# Mako_DSP_Audio_Codec_R1_1.net
KiCad netlist of a schematic drawn in Altium Designer
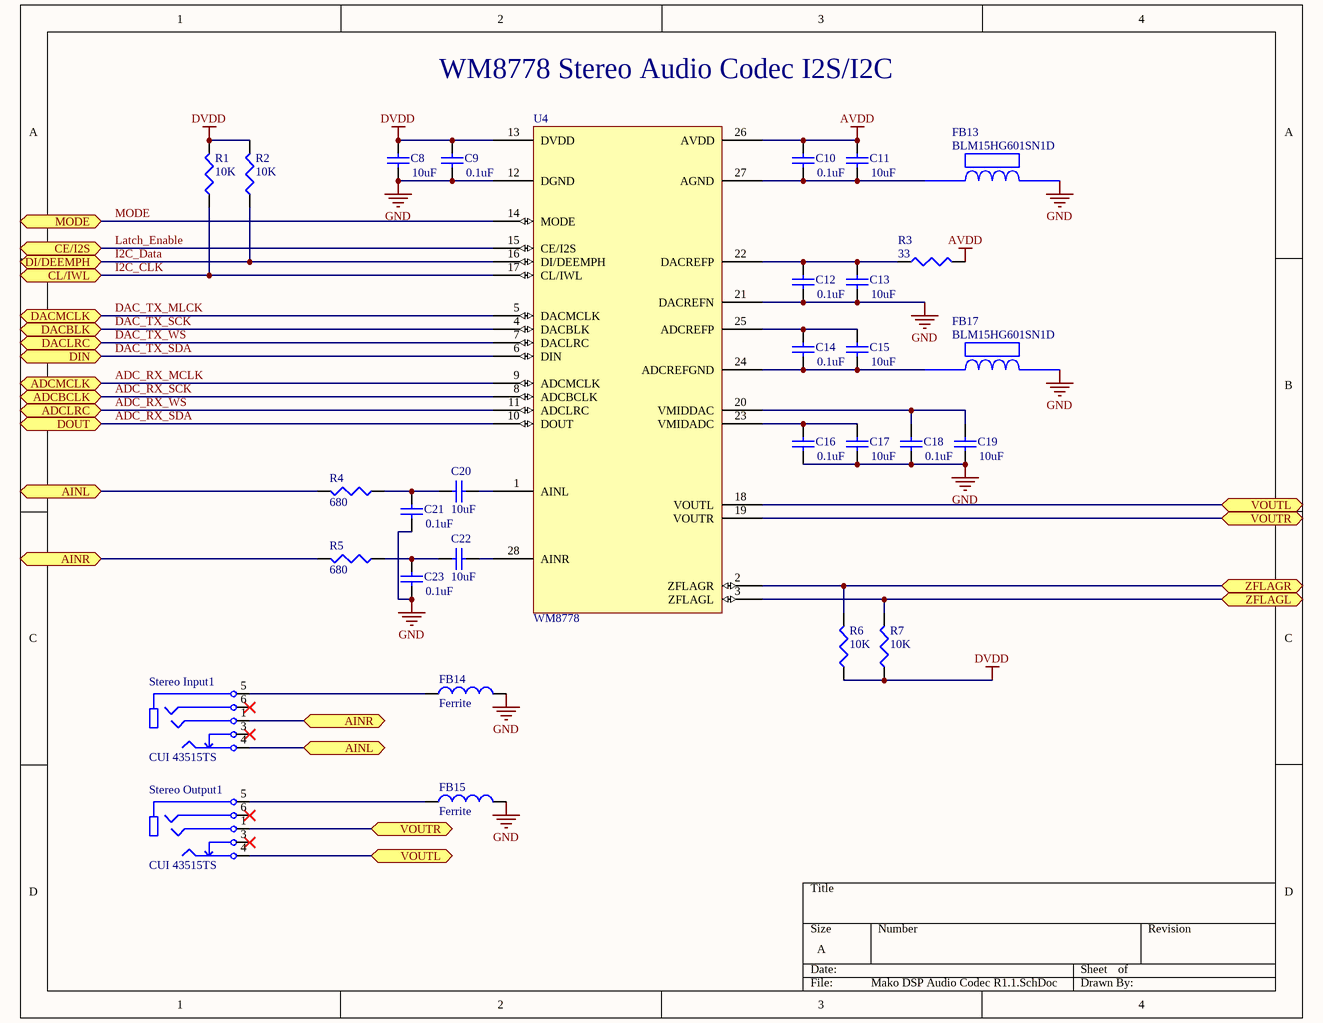
[diagram p0: Mako DSP Audio Codec R1.1.SchDoc]

(export (version "E")
  (design (tool "Eeschema 10.0.6"))
  (components
    (comp (ref "C8")
      (value "10uF")
      (footprint "1608[0603]")
      (description "Capacitor (Semiconductor SIM Model)")
      (fields (field (name "Comment") "Cap Semi") (field (name "PUBLISHER") "Altium Limited"))
      (libsource (lib "Miscellaneous Devices") (part "Cap Semi"))
    )
    (comp (ref "C9")
      (value "0.1uF")
      (footprint "1608[0603]")
      (description "Capacitor (Semiconductor SIM Model)")
      (fields (field (name "Comment") "Cap Semi") (field (name "PUBLISHER") "Altium Limited"))
      (libsource (lib "Miscellaneous Devices") (part "Cap Semi"))
    )
    (comp (ref "C10")
      (value "0.1uF")
      (footprint "1608[0603]")
      (description "Capacitor (Semiconductor SIM Model)")
      (fields (field (name "Comment") "Cap Semi") (field (name "PUBLISHER") "Altium Limited"))
      (libsource (lib "Miscellaneous Devices") (part "Cap Semi"))
    )
    (comp (ref "C11")
      (value "10uF")
      (footprint "1608[0603]")
      (description "Capacitor (Semiconductor SIM Model)")
      (fields (field (name "Comment") "Cap Semi") (field (name "PUBLISHER") "Altium Limited"))
      (libsource (lib "Miscellaneous Devices") (part "Cap Semi"))
    )
    (comp (ref "C12")
      (value "0.1uF")
      (footprint "1608[0603]")
      (description "Capacitor (Semiconductor SIM Model)")
      (fields (field (name "Comment") "Cap Semi") (field (name "PUBLISHER") "Altium Limited"))
      (libsource (lib "Miscellaneous Devices") (part "Cap Semi"))
    )
    (comp (ref "C13")
      (value "10uF")
      (footprint "1608[0603]")
      (description "Capacitor (Semiconductor SIM Model)")
      (fields (field (name "Comment") "Cap Semi") (field (name "PUBLISHER") "Altium Limited"))
      (libsource (lib "Miscellaneous Devices") (part "Cap Semi"))
    )
    (comp (ref "C14")
      (value "0.1uF")
      (footprint "1608[0603]")
      (description "Capacitor (Semiconductor SIM Model)")
      (fields (field (name "Comment") "Cap Semi") (field (name "PUBLISHER") "Altium Limited"))
      (libsource (lib "Miscellaneous Devices") (part "Cap Semi"))
    )
    (comp (ref "C15")
      (value "10uF")
      (footprint "1608[0603]")
      (description "Capacitor (Semiconductor SIM Model)")
      (fields (field (name "Comment") "Cap Semi") (field (name "PUBLISHER") "Altium Limited"))
      (libsource (lib "Miscellaneous Devices") (part "Cap Semi"))
    )
    (comp (ref "C16")
      (value "0.1uF")
      (footprint "1608[0603]")
      (description "Capacitor (Semiconductor SIM Model)")
      (fields (field (name "Comment") "Cap Semi") (field (name "PUBLISHER") "Altium Limited"))
      (libsource (lib "Miscellaneous Devices") (part "Cap Semi"))
    )
    (comp (ref "C17")
      (value "10uF")
      (footprint "1608[0603]")
      (description "Capacitor (Semiconductor SIM Model)")
      (fields (field (name "Comment") "Cap Semi") (field (name "PUBLISHER") "Altium Limited"))
      (libsource (lib "Miscellaneous Devices") (part "Cap Semi"))
    )
    (comp (ref "C18")
      (value "0.1uF")
      (footprint "1608[0603]")
      (description "Capacitor (Semiconductor SIM Model)")
      (fields (field (name "Comment") "Cap Semi") (field (name "PUBLISHER") "Altium Limited"))
      (libsource (lib "Miscellaneous Devices") (part "Cap Semi"))
    )
    (comp (ref "C19")
      (value "10uF")
      (footprint "1608[0603]")
      (description "Capacitor (Semiconductor SIM Model)")
      (fields (field (name "Comment") "Cap Semi") (field (name "PUBLISHER") "Altium Limited"))
      (libsource (lib "Miscellaneous Devices") (part "Cap Semi"))
    )
    (comp (ref "C20")
      (value "10uF")
      (footprint "Panasonic VS B")
      (description "Capacitor (Semiconductor SIM Model)")
      (fields (field (name "Comment") "Cap Semi") (field (name "PUBLISHER") "Altium Limited"))
      (libsource (lib "Miscellaneous Devices") (part "Cap Semi"))
    )
    (comp (ref "C21")
      (value "0.1uF")
      (footprint "SM 0805 - gap trimmed")
      (description "Capacitor (Semiconductor SIM Model)")
      (fields (field (name "Comment") "Cap Semi") (field (name "PUBLISHER") "Altium Limited"))
      (libsource (lib "Miscellaneous Devices") (part "Cap Semi"))
    )
    (comp (ref "C22")
      (value "10uF")
      (footprint "Panasonic VS B")
      (description "Capacitor (Semiconductor SIM Model)")
      (fields (field (name "Comment") "Cap Semi") (field (name "PUBLISHER") "Altium Limited"))
      (libsource (lib "Miscellaneous Devices") (part "Cap Semi"))
    )
    (comp (ref "C23")
      (value "0.1uF")
      (footprint "SM 0805 - gap trimmed")
      (description "Capacitor (Semiconductor SIM Model)")
      (fields (field (name "Comment") "Cap Semi") (field (name "PUBLISHER") "Altium Limited"))
      (libsource (lib "Miscellaneous Devices") (part "Cap Semi"))
    )
    (comp (ref "FB13")
      (value "BLM15HG601SN1D")
      (footprint "BLM18PG121SN1D")
      (libsource (lib "AHD Part Library") (part "BLM15HG601SN1D"))
    )
    (comp (ref "FB14")
      (value "Ferrite")
      (footprint "SM 0805 - gap trimmed")
      (description "Inductor")
      (fields (field (name "PUBLISHER") "Altium Limited"))
      (libsource (lib "Miscellaneous Devices") (part "Inductor"))
    )
    (comp (ref "FB15")
      (value "Ferrite")
      (footprint "SM 0805 - gap trimmed")
      (description "Inductor")
      (fields (field (name "PUBLISHER") "Altium Limited"))
      (libsource (lib "Miscellaneous Devices") (part "Inductor"))
    )
    (comp (ref "FB17")
      (value "BLM15HG601SN1D")
      (footprint "BLM18PG121SN1D")
      (libsource (lib "AHD Part Library") (part "BLM15HG601SN1D"))
    )
    (comp (ref "R1")
      (value "10K")
      (footprint "J1-0603")
      (description "Resistor")
      (fields (field (name "Comment") "Res3") (field (name "PUBLISHER") "Altium Limited"))
      (libsource (lib "Miscellaneous Devices") (part "Res3"))
    )
    (comp (ref "R2")
      (value "10K")
      (footprint "J1-0603")
      (description "Resistor")
      (fields (field (name "Comment") "Res3") (field (name "PUBLISHER") "Altium Limited"))
      (libsource (lib "Miscellaneous Devices") (part "Res3"))
    )
    (comp (ref "R3")
      (value "33")
      (footprint "J1-0603")
      (description "Resistor")
      (fields (field (name "Comment") "Res3") (field (name "PUBLISHER") "Altium Limited"))
      (libsource (lib "Miscellaneous Devices") (part "Res3"))
    )
    (comp (ref "R4")
      (value "680")
      (footprint "SM 0805 - gap trimmed")
      (description "Resistor")
      (fields (field (name "Comment") "Res3") (field (name "PUBLISHER") "Altium Limited"))
      (libsource (lib "Miscellaneous Devices") (part "Res3"))
    )
    (comp (ref "R5")
      (value "680")
      (footprint "SM 0805 - gap trimmed")
      (description "Resistor")
      (fields (field (name "Comment") "Res3") (field (name "PUBLISHER") "Altium Limited"))
      (libsource (lib "Miscellaneous Devices") (part "Res3"))
    )
    (comp (ref "R6")
      (value "10K")
      (footprint "J1-0603")
      (description "Resistor")
      (fields (field (name "Comment") "Res3") (field (name "PUBLISHER") "Altium Limited"))
      (libsource (lib "Miscellaneous Devices") (part "Res3"))
    )
    (comp (ref "R7")
      (value "10K")
      (footprint "J1-0603")
      (description "Resistor")
      (fields (field (name "Comment") "Res3") (field (name "PUBLISHER") "Altium Limited"))
      (libsource (lib "Miscellaneous Devices") (part "Res3"))
    )
    (comp (ref "Stereo Input1")
      (value "CUI 43515TS")
      (footprint "CUI SJ-43515TS")
      (libsource (lib "Adams Altium Library") (part "CUI 43515TS"))
    )
    (comp (ref "Stereo Output1")
      (value "CUI 43515TS")
      (footprint "CUI SJ-43515TS")
      (libsource (lib "Adams Altium Library") (part "CUI 43515TS"))
    )
    (comp (ref "U4")
      (value "WM8778")
      (footprint "WM8778")
      (libsource (lib "Mako DSP Schematic Library") (part "WM8778"))
    )
  )
  (nets
    (net (code "1") (name "/ADC_RX_MCLK") (class "Default")
      (node (ref "U4") (pin "9") (pinfunction "ADCMCLK_9") (pintype "bidirectional"))
    )
    (net (code "2") (name "/ADC_RX_SCK") (class "Default")
      (node (ref "U4") (pin "8") (pinfunction "ADCBCLK_8") (pintype "bidirectional"))
    )
    (net (code "3") (name "/ADC_RX_SDA") (class "Default")
      (node (ref "U4") (pin "10") (pinfunction "DOUT_10") (pintype "bidirectional"))
    )
    (net (code "4") (name "/ADC_RX_WS") (class "Default")
      (node (ref "U4") (pin "11") (pinfunction "ADCLRC_11") (pintype "bidirectional"))
    )
    (net (code "5") (name "/AINL") (class "Default")
      (node (ref "R4") (pin "2") (pinfunction "2_2") (pintype "passive"))
      (node (ref "Stereo Input1") (pin "4") (pinfunction "TIP_4") (pintype "passive"))
    )
    (net (code "6") (name "/AINR") (class "Default")
      (node (ref "R5") (pin "2") (pinfunction "2_2") (pintype "passive"))
      (node (ref "Stereo Input1") (pin "1") (pinfunction "R1_1") (pintype "passive"))
    )
    (net (code "7") (name "/DAC_TX_MLCK") (class "Default")
      (node (ref "U4") (pin "5") (pinfunction "DACMCLK_5") (pintype "bidirectional"))
    )
    (net (code "8") (name "/DAC_TX_SCK") (class "Default")
      (node (ref "U4") (pin "4") (pinfunction "DACBLK_4") (pintype "bidirectional"))
    )
    (net (code "9") (name "/DAC_TX_SDA") (class "Default")
      (node (ref "U4") (pin "6") (pinfunction "DIN_6") (pintype "bidirectional"))
    )
    (net (code "10") (name "/DAC_TX_WS") (class "Default")
      (node (ref "U4") (pin "7") (pinfunction "DACLRC_7") (pintype "bidirectional"))
    )
    (net (code "11") (name "/I2C_CLK") (class "Default")
      (node (ref "R1") (pin "1") (pinfunction "1_1") (pintype "passive"))
      (node (ref "U4") (pin "17") (pinfunction "CL/IWL_17") (pintype "bidirectional"))
    )
    (net (code "12") (name "/I2C_Data") (class "Default")
      (node (ref "R2") (pin "1") (pinfunction "1_1") (pintype "passive"))
      (node (ref "U4") (pin "16") (pinfunction "DI/DEEMPH_16") (pintype "bidirectional"))
    )
    (net (code "13") (name "/Latch_Enable") (class "Default")
      (node (ref "U4") (pin "15") (pinfunction "CE/I2S_15") (pintype "bidirectional"))
    )
    (net (code "14") (name "/MODE") (class "Default")
      (node (ref "U4") (pin "14") (pinfunction "MODE_14") (pintype "bidirectional"))
    )
    (net (code "15") (name "/VOUTL") (class "Default")
      (node (ref "Stereo Output1") (pin "4") (pinfunction "TIP_4") (pintype "passive"))
      (node (ref "U4") (pin "18") (pinfunction "VOUTL_18") (pintype "passive"))
    )
    (net (code "16") (name "/VOUTR") (class "Default")
      (node (ref "Stereo Output1") (pin "1") (pinfunction "R1_1") (pintype "passive"))
      (node (ref "U4") (pin "19") (pinfunction "VOUTR_19") (pintype "passive"))
    )
    (net (code "17") (name "/ZFLAGL") (class "Default")
      (node (ref "R7") (pin "2") (pinfunction "2_2") (pintype "passive"))
      (node (ref "U4") (pin "3") (pinfunction "ZFLAGL_3") (pintype "bidirectional"))
    )
    (net (code "18") (name "/ZFLAGR") (class "Default")
      (node (ref "R6") (pin "2") (pinfunction "2_2") (pintype "passive"))
      (node (ref "U4") (pin "2") (pinfunction "ZFLAGR_2") (pintype "bidirectional"))
    )
    (net (code "19") (name "AVDD") (class "Default")
      (node (ref "C10") (pin "2") (pinfunction "2_2") (pintype "passive"))
      (node (ref "C11") (pin "2") (pinfunction "2_2") (pintype "passive"))
      (node (ref "R3") (pin "2") (pinfunction "2_2") (pintype "passive"))
      (node (ref "U4") (pin "26") (pinfunction "AVDD_26") (pintype "passive"))
    )
    (net (code "20") (name "DVDD") (class "Default")
      (node (ref "C8") (pin "2") (pinfunction "2_2") (pintype "passive"))
      (node (ref "C9") (pin "2") (pinfunction "2_2") (pintype "passive"))
      (node (ref "R1") (pin "2") (pinfunction "2_2") (pintype "passive"))
      (node (ref "R2") (pin "2") (pinfunction "2_2") (pintype "passive"))
      (node (ref "R6") (pin "1") (pinfunction "1_1") (pintype "passive"))
      (node (ref "R7") (pin "1") (pinfunction "1_1") (pintype "passive"))
      (node (ref "U4") (pin "13") (pinfunction "DVDD_13") (pintype "passive"))
    )
    (net (code "21") (name "GND") (class "Default")
      (node (ref "C12") (pin "1") (pinfunction "1_1") (pintype "passive"))
      (node (ref "C13") (pin "1") (pinfunction "1_1") (pintype "passive"))
      (node (ref "C16") (pin "1") (pinfunction "1_1") (pintype "passive"))
      (node (ref "C17") (pin "1") (pinfunction "1_1") (pintype "passive"))
      (node (ref "C18") (pin "1") (pinfunction "1_1") (pintype "passive"))
      (node (ref "C19") (pin "1") (pinfunction "1_1") (pintype "passive"))
      (node (ref "C21") (pin "1") (pinfunction "1_1") (pintype "passive"))
      (node (ref "C23") (pin "1") (pinfunction "1_1") (pintype "passive"))
      (node (ref "C8") (pin "1") (pinfunction "1_1") (pintype "passive"))
      (node (ref "C9") (pin "1") (pinfunction "1_1") (pintype "passive"))
      (node (ref "FB13") (pin "2") (pinfunction "2_2") (pintype "passive"))
      (node (ref "FB14") (pin "2") (pinfunction "2_2") (pintype "passive"))
      (node (ref "FB15") (pin "2") (pinfunction "2_2") (pintype "passive"))
      (node (ref "FB17") (pin "2") (pinfunction "2_2") (pintype "passive"))
      (node (ref "U4") (pin "12") (pinfunction "DGND_12") (pintype "passive"))
      (node (ref "U4") (pin "21") (pinfunction "DACREFN_21") (pintype "passive"))
    )
    (net (code "22") (name "Net-(C20-Pad2)") (class "Default")
      (node (ref "C20") (pin "2") (pinfunction "2_2") (pintype "passive"))
      (node (ref "C21") (pin "2") (pinfunction "2_2") (pintype "passive"))
      (node (ref "R4") (pin "1") (pinfunction "1_1") (pintype "passive"))
    )
    (net (code "23") (name "Net-(C22-Pad2)") (class "Default")
      (node (ref "C22") (pin "2") (pinfunction "2_2") (pintype "passive"))
      (node (ref "C23") (pin "2") (pinfunction "2_2") (pintype "passive"))
      (node (ref "R5") (pin "1") (pinfunction "1_1") (pintype "passive"))
    )
    (net (code "24") (name "Net-(Stereo Input1-SLEEVE)") (class "Default")
      (node (ref "FB14") (pin "1") (pinfunction "1_1") (pintype "passive"))
      (node (ref "Stereo Input1") (pin "5") (pinfunction "SLEEVE_5") (pintype "passive"))
    )
    (net (code "25") (name "Net-(Stereo Output1-SLEEVE)") (class "Default")
      (node (ref "FB15") (pin "1") (pinfunction "1_1") (pintype "passive"))
      (node (ref "Stereo Output1") (pin "5") (pinfunction "SLEEVE_5") (pintype "passive"))
    )
    (net (code "26") (name "Net-(U4-ADCREFGND)") (class "Default")
      (node (ref "C14") (pin "1") (pinfunction "1_1") (pintype "passive"))
      (node (ref "C15") (pin "1") (pinfunction "1_1") (pintype "passive"))
      (node (ref "FB17") (pin "1") (pinfunction "1_1") (pintype "passive"))
      (node (ref "U4") (pin "24") (pinfunction "ADCREFGND_24") (pintype "passive"))
    )
    (net (code "27") (name "Net-(U4-ADCREFP)") (class "Default")
      (node (ref "C14") (pin "2") (pinfunction "2_2") (pintype "passive"))
      (node (ref "C15") (pin "2") (pinfunction "2_2") (pintype "passive"))
      (node (ref "U4") (pin "25") (pinfunction "ADCREFP_25") (pintype "passive"))
    )
    (net (code "28") (name "Net-(U4-AGND)") (class "Default")
      (node (ref "C10") (pin "1") (pinfunction "1_1") (pintype "passive"))
      (node (ref "C11") (pin "1") (pinfunction "1_1") (pintype "passive"))
      (node (ref "FB13") (pin "1") (pinfunction "1_1") (pintype "passive"))
      (node (ref "U4") (pin "27") (pinfunction "AGND_27") (pintype "passive"))
    )
    (net (code "29") (name "Net-(U4-AINL)") (class "Default")
      (node (ref "C20") (pin "1") (pinfunction "1_1") (pintype "passive"))
      (node (ref "U4") (pin "1") (pinfunction "AINL_1") (pintype "passive"))
    )
    (net (code "30") (name "Net-(U4-AINR)") (class "Default")
      (node (ref "C22") (pin "1") (pinfunction "1_1") (pintype "passive"))
      (node (ref "U4") (pin "28") (pinfunction "AINR_28") (pintype "passive"))
    )
    (net (code "31") (name "Net-(U4-DACREFP)") (class "Default")
      (node (ref "C12") (pin "2") (pinfunction "2_2") (pintype "passive"))
      (node (ref "C13") (pin "2") (pinfunction "2_2") (pintype "passive"))
      (node (ref "R3") (pin "1") (pinfunction "1_1") (pintype "passive"))
      (node (ref "U4") (pin "22") (pinfunction "DACREFP_22") (pintype "passive"))
    )
    (net (code "32") (name "Net-(U4-VMIDADC)") (class "Default")
      (node (ref "C16") (pin "2") (pinfunction "2_2") (pintype "passive"))
      (node (ref "C17") (pin "2") (pinfunction "2_2") (pintype "passive"))
      (node (ref "U4") (pin "23") (pinfunction "VMIDADC_23") (pintype "passive"))
    )
    (net (code "33") (name "Net-(U4-VMIDDAC)") (class "Default")
      (node (ref "C18") (pin "2") (pinfunction "2_2") (pintype "passive"))
      (node (ref "C19") (pin "2") (pinfunction "2_2") (pintype "passive"))
      (node (ref "U4") (pin "20") (pinfunction "VMIDDAC_20") (pintype "passive"))
    )
    (net (code "34") (name "unconnected-(Stereo Input1-R2-Pad6)") (class "Default")
      (node (ref "Stereo Input1") (pin "6") (pinfunction "R2_6") (pintype "passive+no_connect"))
    )
    (net (code "35") (name "unconnected-(Stereo Input1-TS-Pad3)") (class "Default")
      (node (ref "Stereo Input1") (pin "3") (pinfunction "TS_3") (pintype "passive+no_connect"))
    )
    (net (code "36") (name "unconnected-(Stereo Output1-R2-Pad6)") (class "Default")
      (node (ref "Stereo Output1") (pin "6") (pinfunction "R2_6") (pintype "passive+no_connect"))
    )
    (net (code "37") (name "unconnected-(Stereo Output1-TS-Pad3)") (class "Default")
      (node (ref "Stereo Output1") (pin "3") (pinfunction "TS_3") (pintype "passive+no_connect"))
    )
  )
)
